# Adafruit_Feather_Teensy3_Adapter.net
KiCad netlist of a schematic drawn in EAGLE
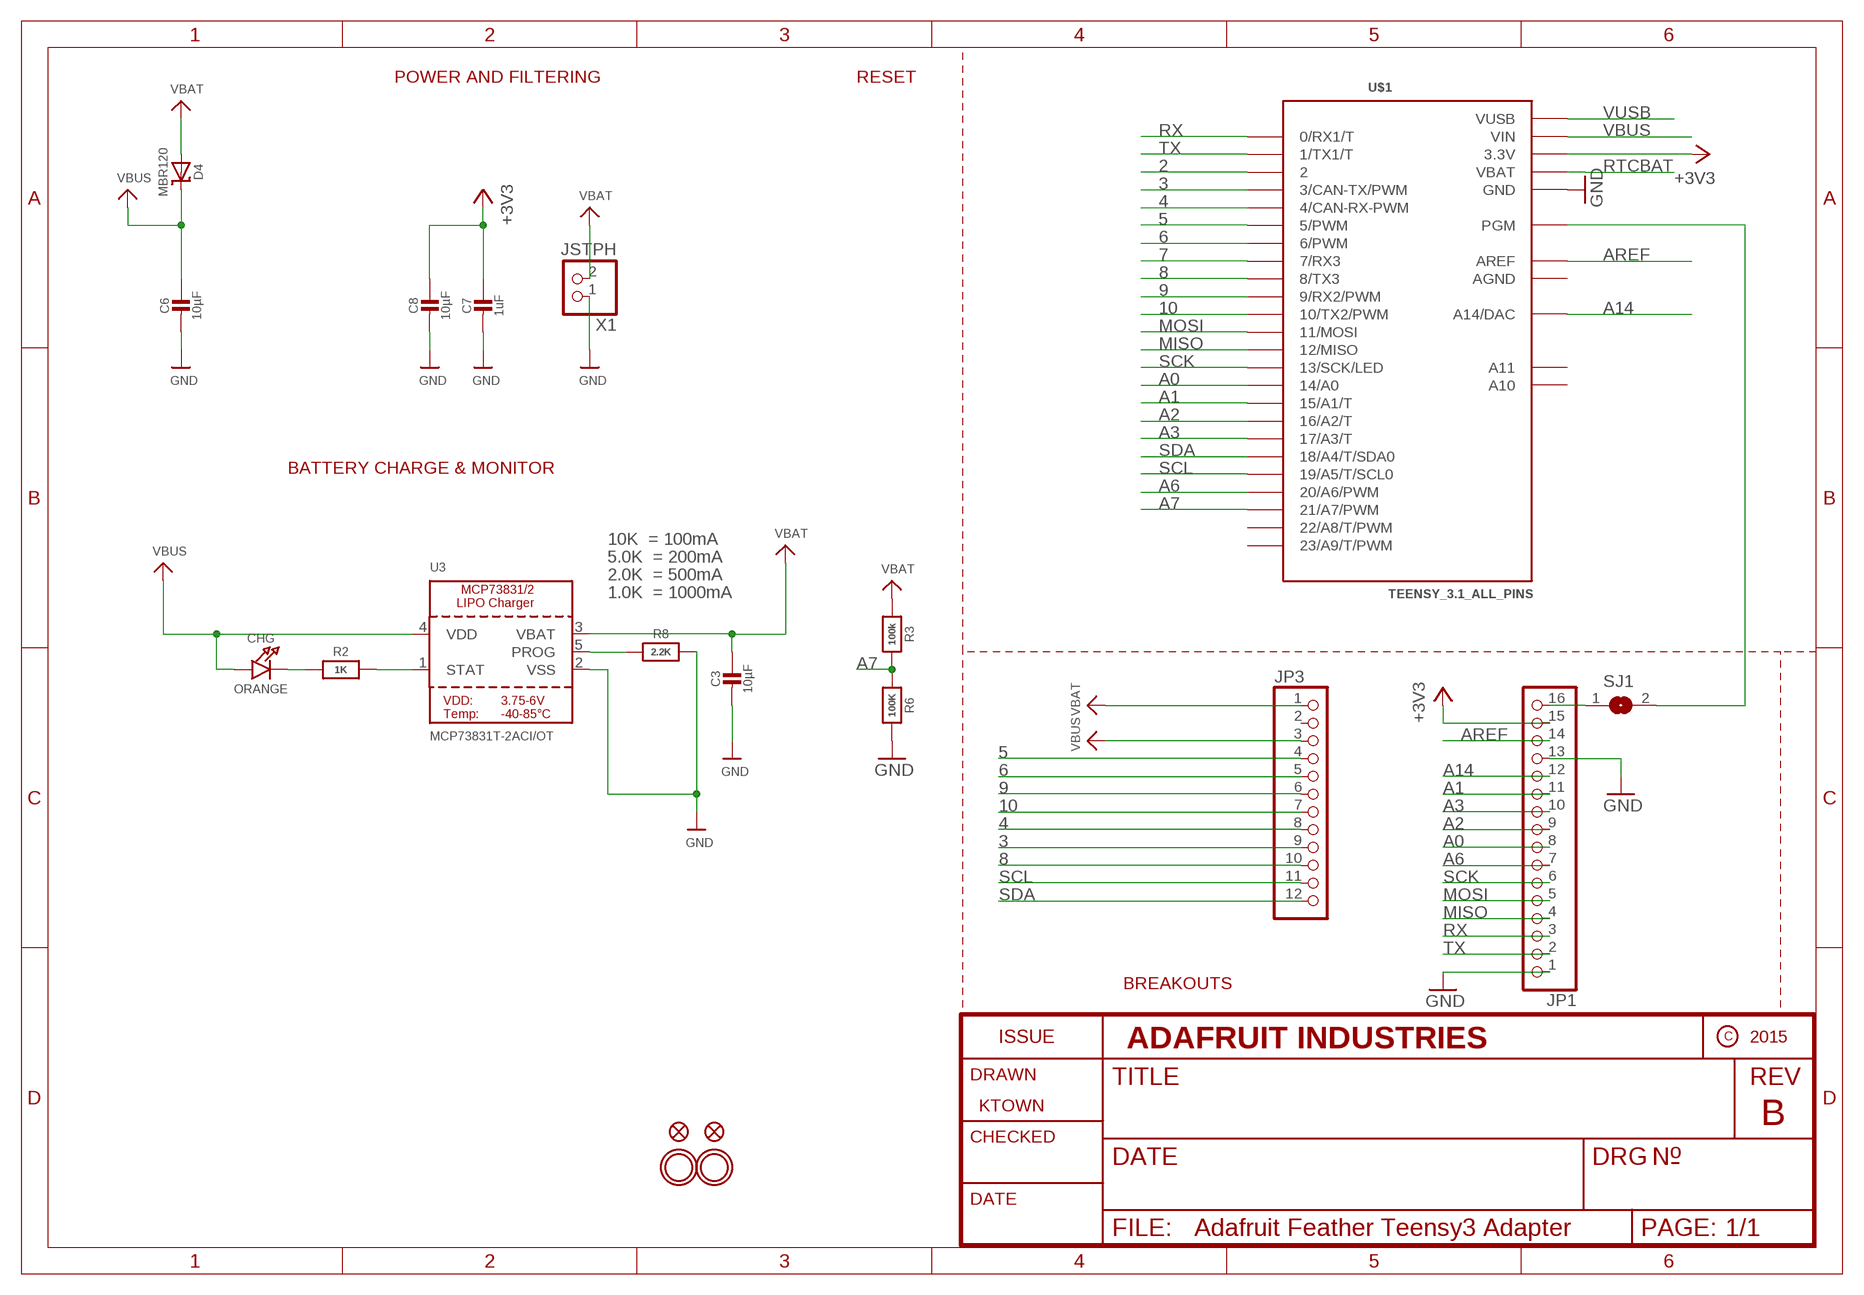
[diagram p0: schematic, sheet 1]

(export (version "E")
  (design (tool "Eeschema 10.0.6"))
  (components
    (comp (ref "C3")
      (value "10µF")
      (footprint "eagle-import:0805-NO")
      (libsource (lib "eagle-import") (part "CAP_CERAMIC0805-NOOUTLINE"))
    )
    (comp (ref "C6")
      (value "10µF")
      (footprint "eagle-import:0805-NO")
      (libsource (lib "eagle-import") (part "CAP_CERAMIC0805-NOOUTLINE"))
    )
    (comp (ref "C7")
      (value "1uF")
      (footprint "eagle-import:0603-NO")
      (libsource (lib "eagle-import") (part "CAP_CERAMIC0603_NO"))
    )
    (comp (ref "C8")
      (value "10µF")
      (footprint "eagle-import:0805-NO")
      (libsource (lib "eagle-import") (part "CAP_CERAMIC0805-NOOUTLINE"))
    )
    (comp (ref "CHG")
      (value "ORANGE")
      (footprint "eagle-import:CHIPLED_0805_NOOUTLINE")
      (libsource (lib "eagle-import") (part "LED0805_NOOUTLINE"))
    )
    (comp (ref "D4")
      (value "MBR120")
      (footprint "eagle-import:SOD-123")
      (libsource (lib "eagle-import") (part "DIODE-SCHOTTKYSOD-123"))
    )
    (comp (ref "JP1")
      (value "HEADER-1X16ROUND")
      (footprint "eagle-import:1X16_ROUND")
      (libsource (lib "eagle-import") (part "HEADER-1X16ROUND"))
    )
    (comp (ref "JP3")
      (value "HEADER-1X12")
      (footprint "eagle-import:1X12_ROUND")
      (libsource (lib "eagle-import") (part "HEADER-1X12"))
    )
    (comp (ref "R2")
      (value "1K")
      (footprint "eagle-import:0603-NO")
      (libsource (lib "eagle-import") (part "RESISTOR_0603_NOOUT"))
    )
    (comp (ref "R3")
      (value "100k")
      (footprint "eagle-import:0603-NO")
      (libsource (lib "eagle-import") (part "RESISTOR_0603_NOOUT"))
    )
    (comp (ref "R6")
      (value "100K")
      (footprint "eagle-import:0603-NO")
      (libsource (lib "eagle-import") (part "RESISTOR_0603_NOOUT"))
    )
    (comp (ref "R8")
      (value "2.2K")
      (footprint "eagle-import:0603-NO")
      (libsource (lib "eagle-import") (part "RESISTOR_0603_NOOUT"))
    )
    (comp (ref "SJ1")
      (value "SOLDERJUMPERCLOSED")
      (footprint "eagle-import:SOLDERJUMPER_CLOSEDWIRE")
      (libsource (lib "eagle-import") (part "SOLDERJUMPERCLOSED"))
    )
    (comp (ref "U$1")
      (value "TEENSY_3.1_ALL_PINS")
      (footprint "eagle-import:TEENSY3-ALL_PINS")
      (libsource (lib "eagle-import") (part "TEENSY_3.1_ALL_PINS"))
    )
    (comp (ref "U$31")
      (value "MOUNTINGHOLE2.5")
      (footprint "eagle-import:MOUNTINGHOLE_2.5_PLATED")
      (libsource (lib "eagle-import") (part "MOUNTINGHOLE2.5"))
    )
    (comp (ref "U$32")
      (value "MOUNTINGHOLE2.5")
      (footprint "eagle-import:MOUNTINGHOLE_2.5_PLATED")
      (libsource (lib "eagle-import") (part "MOUNTINGHOLE2.5"))
    )
    (comp (ref "U$34")
      (value "FIDUCIAL\"\"")
      (footprint "eagle-import:FIDUCIAL_1MM")
      (libsource (lib "eagle-import") (part "FIDUCIAL{dblquote}{dblquote}"))
    )
    (comp (ref "U$35")
      (value "FIDUCIAL\"\"")
      (footprint "eagle-import:FIDUCIAL_1MM")
      (libsource (lib "eagle-import") (part "FIDUCIAL{dblquote}{dblquote}"))
    )
    (comp (ref "U3")
      (value "MCP73831T-2ACI/OT")
      (footprint "eagle-import:SOT23-5")
      (libsource (lib "eagle-import") (part "MCP73831/2"))
    )
    (comp (ref "X1")
      (value "JSTPH")
      (footprint "eagle-import:JSTPH2")
      (libsource (lib "eagle-import") (part "CON_JST_PH_2PIN"))
    )
  )
  (nets
    (net (code "1") (name "+3V3") (class "Default")
      (node (ref "C7") (pin "1") (pinfunction "1_1") (pintype "passive"))
      (node (ref "C8") (pin "1") (pinfunction "1_1") (pintype "passive"))
      (node (ref "JP1") (pin "15") (pinfunction "15_15") (pintype "passive"))
      (node (ref "U$1") (pin "3.3V") (pinfunction "3.3V_3.3V") (pintype "power_in"))
      (node (ref "U$1") (pin "3.3V1") (pinfunction "3.3V_3.3V1") (pintype "power_in"))
    )
    (net (code "2") (name "/2") (class "Default")
      (node (ref "U$1") (pin "2") (pinfunction "2_2") (pintype "bidirectional"))
    )
    (net (code "3") (name "/3") (class "Default")
      (node (ref "JP3") (pin "9") (pinfunction "9_9") (pintype "passive"))
      (node (ref "U$1") (pin "3") (pinfunction "3/CAN-TX/PWM_3") (pintype "bidirectional"))
    )
    (net (code "4") (name "/4") (class "Default")
      (node (ref "JP3") (pin "8") (pinfunction "8_8") (pintype "passive"))
      (node (ref "U$1") (pin "4") (pinfunction "4/CAN-RX-PWM_4") (pintype "bidirectional"))
    )
    (net (code "5") (name "/5") (class "Default")
      (node (ref "JP3") (pin "4") (pinfunction "4_4") (pintype "passive"))
      (node (ref "U$1") (pin "5") (pinfunction "5/PWM_5") (pintype "bidirectional"))
    )
    (net (code "6") (name "/6") (class "Default")
      (node (ref "JP3") (pin "5") (pinfunction "5_5") (pintype "passive"))
      (node (ref "U$1") (pin "6") (pinfunction "6/PWM_6") (pintype "bidirectional"))
    )
    (net (code "7") (name "/7") (class "Default")
      (node (ref "U$1") (pin "7") (pinfunction "7/RX3_7") (pintype "bidirectional"))
    )
    (net (code "8") (name "/8") (class "Default")
      (node (ref "JP3") (pin "10") (pinfunction "10_10") (pintype "passive"))
      (node (ref "U$1") (pin "8") (pinfunction "8/TX3_8") (pintype "bidirectional"))
    )
    (net (code "9") (name "/9") (class "Default")
      (node (ref "JP3") (pin "6") (pinfunction "6_6") (pintype "passive"))
      (node (ref "U$1") (pin "9") (pinfunction "9/RX2/PWM_9") (pintype "bidirectional"))
    )
    (net (code "10") (name "/10") (class "Default")
      (node (ref "JP3") (pin "7") (pinfunction "7_7") (pintype "passive"))
      (node (ref "U$1") (pin "10") (pinfunction "10/TX2/PWM_10") (pintype "bidirectional"))
    )
    (net (code "11") (name "/A0") (class "Default")
      (node (ref "JP1") (pin "8") (pinfunction "8_8") (pintype "passive"))
      (node (ref "U$1") (pin "14/A0") (pinfunction "14/A0_14/A0") (pintype "bidirectional"))
    )
    (net (code "12") (name "/A1") (class "Default")
      (node (ref "JP1") (pin "11") (pinfunction "11_11") (pintype "passive"))
      (node (ref "U$1") (pin "15/A1") (pinfunction "15/A1/T_15/A1") (pintype "bidirectional"))
    )
    (net (code "13") (name "/A2") (class "Default")
      (node (ref "JP1") (pin "9") (pinfunction "9_9") (pintype "passive"))
      (node (ref "U$1") (pin "16/A2") (pinfunction "16/A2/T_16/A2") (pintype "bidirectional"))
    )
    (net (code "14") (name "/A3") (class "Default")
      (node (ref "JP1") (pin "10") (pinfunction "10_10") (pintype "passive"))
      (node (ref "U$1") (pin "17/A3") (pinfunction "17/A3/T_17/A3") (pintype "bidirectional"))
    )
    (net (code "15") (name "/A6") (class "Default")
      (node (ref "JP1") (pin "7") (pinfunction "7_7") (pintype "passive"))
      (node (ref "U$1") (pin "20/A6") (pinfunction "20/A6/PWM_20/A6") (pintype "bidirectional"))
    )
    (net (code "16") (name "/A7") (class "Default")
      (node (ref "R3") (pin "2") (pinfunction "2_2") (pintype "passive"))
      (node (ref "R6") (pin "1") (pinfunction "1_1") (pintype "passive"))
      (node (ref "U$1") (pin "21/A7") (pinfunction "21/A7/PWM_21/A7") (pintype "bidirectional"))
    )
    (net (code "17") (name "/A14") (class "Default")
      (node (ref "JP1") (pin "12") (pinfunction "12_12") (pintype "passive"))
      (node (ref "U$1") (pin "RESET/DAC") (pinfunction "A14/DAC_RESET/DAC") (pintype "bidirectional"))
    )
    (net (code "18") (name "/AGND") (class "Default")
      (node (ref "U$1") (pin "AGND") (pinfunction "AGND_AGND") (pintype "power_in"))
    )
    (net (code "19") (name "/AREF") (class "Default")
      (node (ref "JP1") (pin "14") (pinfunction "14_14") (pintype "passive"))
      (node (ref "U$1") (pin "AREF") (pinfunction "AREF_AREF") (pintype "power_in"))
    )
    (net (code "20") (name "/MISO") (class "Default")
      (node (ref "JP1") (pin "4") (pinfunction "4_4") (pintype "passive"))
      (node (ref "U$1") (pin "12") (pinfunction "12/MISO_12") (pintype "bidirectional"))
    )
    (net (code "21") (name "/MOSI") (class "Default")
      (node (ref "JP1") (pin "5") (pinfunction "5_5") (pintype "passive"))
      (node (ref "U$1") (pin "11") (pinfunction "11/MOSI_11") (pintype "bidirectional"))
    )
    (net (code "22") (name "/RTCBAT") (class "Default")
      (node (ref "U$1") (pin "VBAT") (pinfunction "VBAT_VBAT") (pintype "power_in"))
    )
    (net (code "23") (name "/RX") (class "Default")
      (node (ref "JP1") (pin "3") (pinfunction "3_3") (pintype "passive"))
      (node (ref "U$1") (pin "0") (pinfunction "0/RX1/T_0") (pintype "bidirectional"))
    )
    (net (code "24") (name "/SCK") (class "Default")
      (node (ref "JP1") (pin "6") (pinfunction "6_6") (pintype "passive"))
      (node (ref "U$1") (pin "13") (pinfunction "13/SCK/LED_13") (pintype "bidirectional"))
    )
    (net (code "25") (name "/SCL") (class "Default")
      (node (ref "JP3") (pin "11") (pinfunction "11_11") (pintype "passive"))
      (node (ref "U$1") (pin "19/A5") (pinfunction "19/A5/T/SCL0_19/A5") (pintype "bidirectional"))
    )
    (net (code "26") (name "/SDA") (class "Default")
      (node (ref "JP3") (pin "12") (pinfunction "12_12") (pintype "passive"))
      (node (ref "U$1") (pin "18/A4") (pinfunction "18/A4/T/SDA0_18/A4") (pintype "bidirectional"))
    )
    (net (code "27") (name "/TX") (class "Default")
      (node (ref "JP1") (pin "2") (pinfunction "2_2") (pintype "passive"))
      (node (ref "U$1") (pin "1") (pinfunction "1/TX1/T_1") (pintype "bidirectional"))
    )
    (net (code "28") (name "/VUSB") (class "Default")
      (node (ref "U$1") (pin "VUSB") (pinfunction "VUSB_VUSB") (pintype "power_in"))
    )
    (net (code "29") (name "GND") (class "Default")
      (node (ref "C3") (pin "2") (pinfunction "2_2") (pintype "passive"))
      (node (ref "C6") (pin "2") (pinfunction "2_2") (pintype "passive"))
      (node (ref "C7") (pin "2") (pinfunction "2_2") (pintype "passive"))
      (node (ref "C8") (pin "2") (pinfunction "2_2") (pintype "passive"))
      (node (ref "JP1") (pin "1") (pinfunction "1_1") (pintype "passive"))
      (node (ref "JP1") (pin "13") (pinfunction "13_13") (pintype "passive"))
      (node (ref "R6") (pin "2") (pinfunction "2_2") (pintype "passive"))
      (node (ref "R8") (pin "2") (pinfunction "2_2") (pintype "passive"))
      (node (ref "U$1") (pin "GND") (pinfunction "GND_GND") (pintype "power_in"))
      (node (ref "U$1") (pin "GND1") (pinfunction "GND_GND1") (pintype "power_in"))
      (node (ref "U3") (pin "2") (pinfunction "VSS_2") (pintype "power_in"))
      (node (ref "X1") (pin "1") (pinfunction "1_1") (pintype "passive"))
    )
    (net (code "30") (name "Net-(CHG-PadC)") (class "Default")
      (node (ref "CHG") (pin "C") (pinfunction "C_C") (pintype "passive"))
      (node (ref "R2") (pin "1") (pinfunction "1_1") (pintype "passive"))
    )
    (net (code "31") (name "Net-(JP1-Pad16)") (class "Default")
      (node (ref "JP1") (pin "16") (pinfunction "16_16") (pintype "passive"))
      (node (ref "SJ1") (pin "1") (pinfunction "1_1") (pintype "passive"))
    )
    (net (code "32") (name "Net-(SJ1-Pad2)") (class "Default")
      (node (ref "SJ1") (pin "2") (pinfunction "2_2") (pintype "passive"))
      (node (ref "U$1") (pin "PGM") (pinfunction "PGM_PGM") (pintype "bidirectional"))
    )
    (net (code "33") (name "Net-(U3-PROG)") (class "Default")
      (node (ref "R8") (pin "1") (pinfunction "1_1") (pintype "passive"))
      (node (ref "U3") (pin "5") (pinfunction "PROG_5") (pintype "input"))
    )
    (net (code "34") (name "Net-(U3-STAT)") (class "Default")
      (node (ref "R2") (pin "2") (pinfunction "2_2") (pintype "passive"))
      (node (ref "U3") (pin "1") (pinfunction "STAT_1") (pintype "output"))
    )
    (net (code "35") (name "VBAT") (class "Default")
      (node (ref "C3") (pin "1") (pinfunction "1_1") (pintype "passive"))
      (node (ref "D4") (pin "A") (pinfunction "A_A") (pintype "passive"))
      (node (ref "JP3") (pin "1") (pinfunction "1_1") (pintype "passive"))
      (node (ref "R3") (pin "1") (pinfunction "1_1") (pintype "passive"))
      (node (ref "U3") (pin "3") (pinfunction "VBAT_3") (pintype "power_in"))
      (node (ref "X1") (pin "2") (pinfunction "2_2") (pintype "passive"))
    )
    (net (code "36") (name "VBUS") (class "Default")
      (node (ref "C6") (pin "1") (pinfunction "1_1") (pintype "passive"))
      (node (ref "CHG") (pin "A") (pinfunction "A_A") (pintype "passive"))
      (node (ref "D4") (pin "C") (pinfunction "C_C") (pintype "passive"))
      (node (ref "JP3") (pin "3") (pinfunction "3_3") (pintype "passive"))
      (node (ref "U$1") (pin "VIN") (pinfunction "VIN_VIN") (pintype "power_in"))
      (node (ref "U3") (pin "4") (pinfunction "VDD_4") (pintype "power_in"))
    )
    (net (code "37") (name "unconnected-(JP3-Pad2)") (class "Default")
      (node (ref "JP3") (pin "2") (pinfunction "2_2") (pintype "passive"))
    )
    (net (code "38") (name "unconnected-(U$1-22{slash}A8{slash}T{slash}PWM-Pad22{slash}A8)") (class "Default")
      (node (ref "U$1") (pin "22/A8") (pinfunction "22/A8/T/PWM_22/A8") (pintype "bidirectional"))
    )
    (net (code "39") (name "unconnected-(U$1-23{slash}A9{slash}T{slash}PWM-Pad23{slash}A9)") (class "Default")
      (node (ref "U$1") (pin "23/A9") (pinfunction "23/A9/T/PWM_23/A9") (pintype "bidirectional"))
    )
    (net (code "40") (name "unconnected-(U$1-PadA10)") (class "Default")
      (node (ref "U$1") (pin "A10") (pinfunction "A10_A10") (pintype "bidirectional"))
    )
    (net (code "41") (name "unconnected-(U$1-PadA11)") (class "Default")
      (node (ref "U$1") (pin "A11") (pinfunction "A11_A11") (pintype "bidirectional"))
    )
  )
)
